# sd_tos_dip32.net
KiCad netlist of a schematic drawn in EAGLE
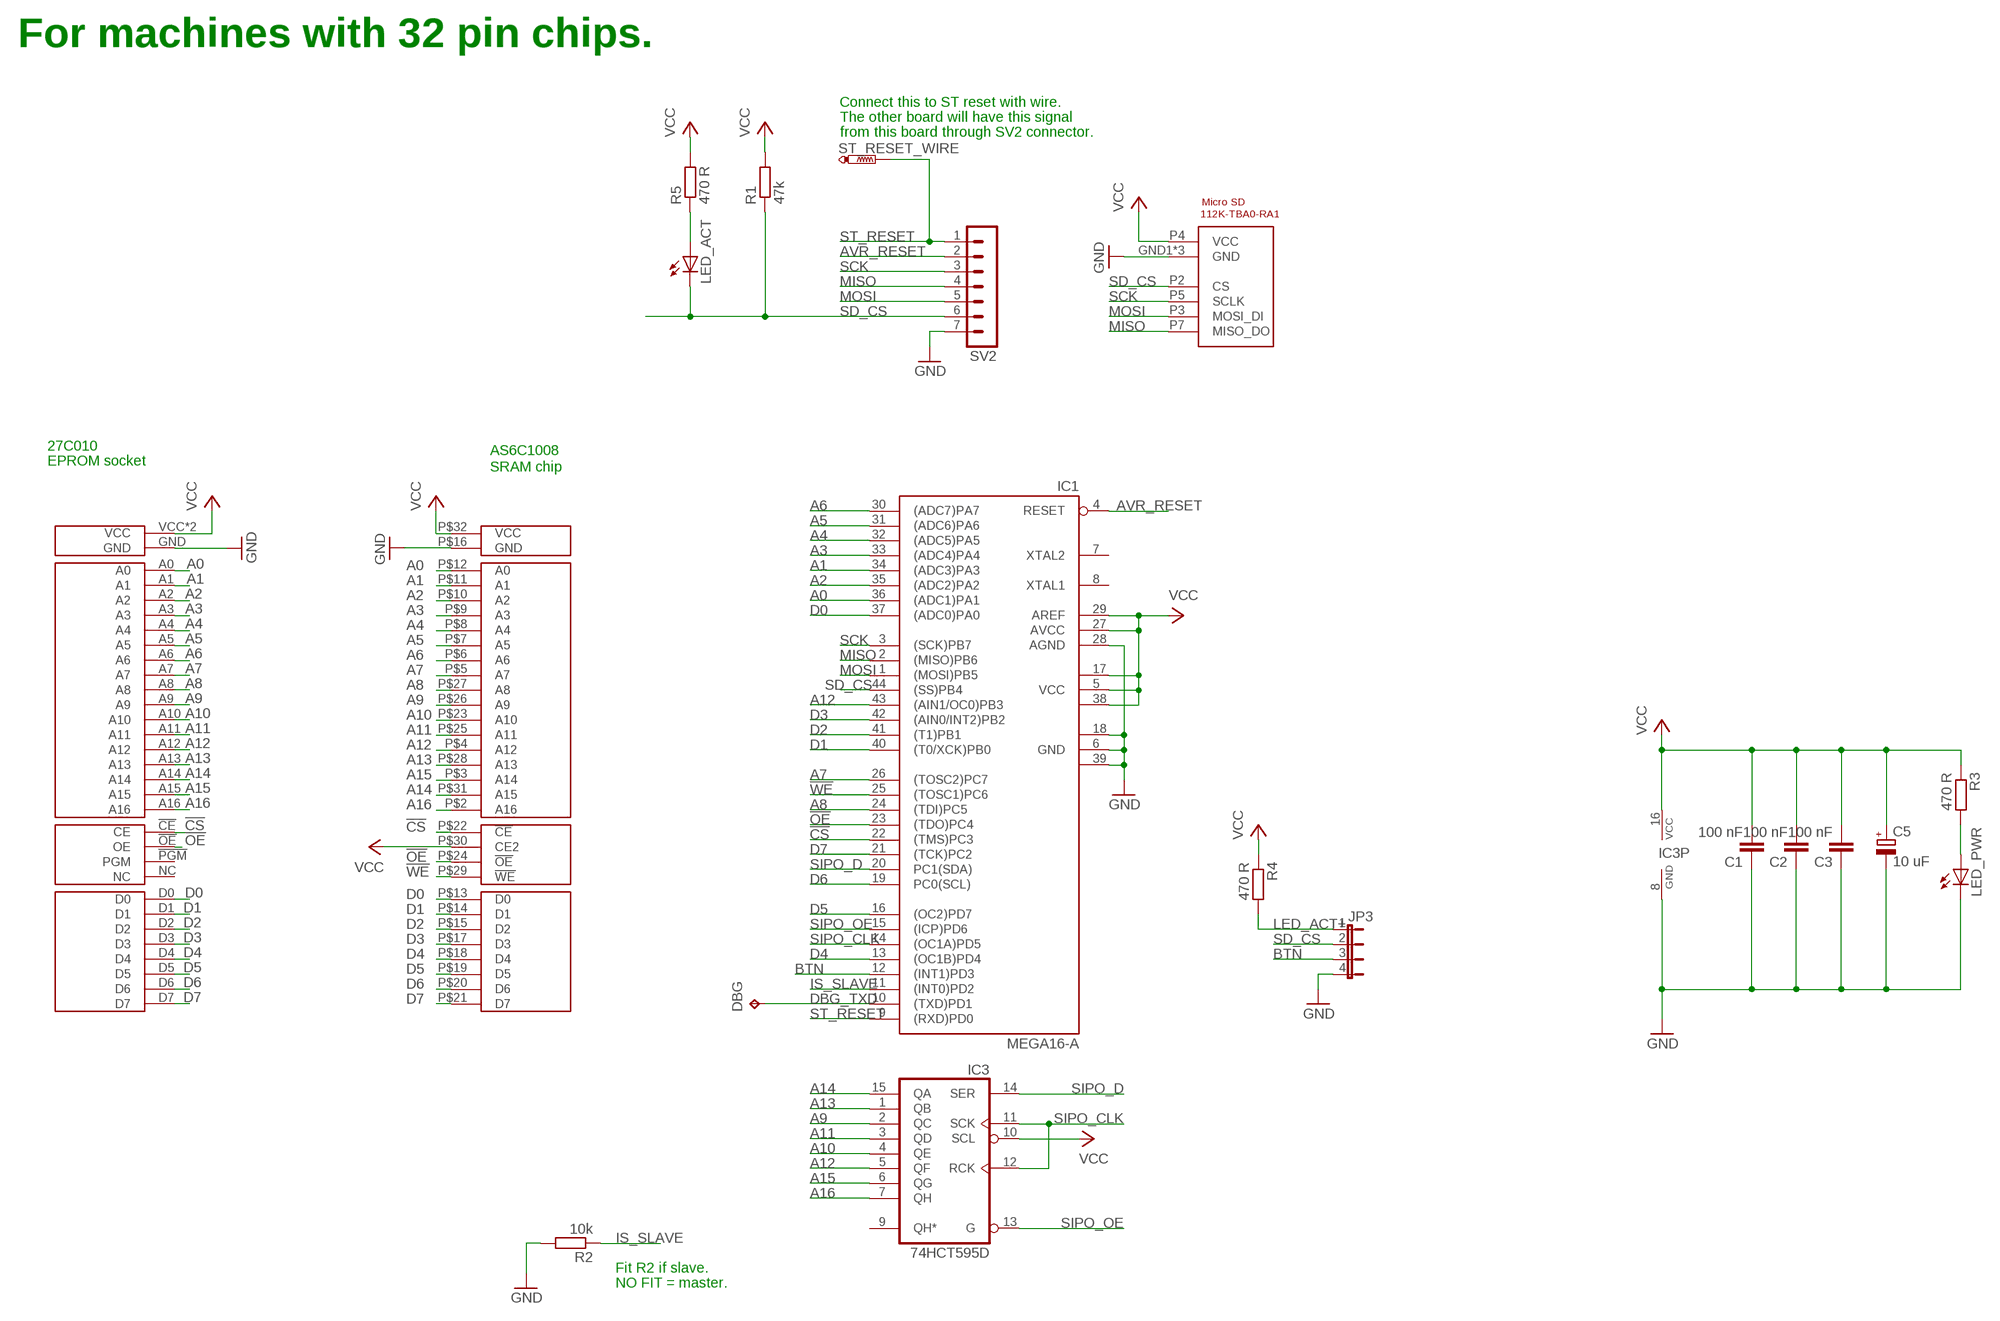
[diagram p0: schematic, sheet 1]

(export (version "E")
  (design (tool "Eeschema 10.0.6"))
  (components
    (comp (ref "C1")
      (value "100 nF")
      (footprint "eagle-import:C0603")
      (libsource (lib "eagle-import") (part "C-EUC0603"))
    )
    (comp (ref "C2")
      (value "100 nF")
      (footprint "eagle-import:C0603")
      (libsource (lib "eagle-import") (part "C-EUC0603"))
    )
    (comp (ref "C3")
      (value "100 nF")
      (footprint "eagle-import:C0603")
      (libsource (lib "eagle-import") (part "C-EUC0603"))
    )
    (comp (ref "C5")
      (value "10 uF")
      (footprint "eagle-import:SANYO-OSCON_SMD_B6")
      (libsource (lib "eagle-import") (part "CPOL-EUSANYO_SMD_B6"))
    )
    (comp (ref "DBG")
      (value "TPB1,27")
      (footprint "eagle-import:B1,27")
      (libsource (lib "eagle-import") (part "TPB1,27"))
    )
    (comp (ref "IC1")
      (value "MEGA16-A")
      (footprint "eagle-import:TQFP44")
      (libsource (lib "eagle-import") (part "MEGA16-A"))
    )
    (comp (ref "IC3")
      (value "74HCT595D")
      (footprint "eagle-import:SO16")
      (libsource (lib "eagle-import") (part "74595DHCT"))
    )
    (comp (ref "JP3")
      (value "JP4E")
      (footprint "eagle-import:JP4")
      (libsource (lib "eagle-import") (part "JP4E"))
    )
    (comp (ref "LED_ACT")
      (value "LEDCHIP-LED0805")
      (footprint "eagle-import:CHIP-LED0805")
      (libsource (lib "eagle-import") (part "LEDCHIP-LED0805"))
    )
    (comp (ref "LED_PWR")
      (value "LEDCHIP-LED0805")
      (footprint "eagle-import:CHIP-LED0805")
      (libsource (lib "eagle-import") (part "LEDCHIP-LED0805"))
    )
    (comp (ref "R1")
      (value "47k")
      (footprint "eagle-import:R0603")
      (libsource (lib "eagle-import") (part "R-EU_R0603"))
    )
    (comp (ref "R2")
      (value "10k")
      (footprint "eagle-import:R0603")
      (libsource (lib "eagle-import") (part "R-EU_R0603"))
    )
    (comp (ref "R3")
      (value "470 R")
      (footprint "eagle-import:R0603")
      (libsource (lib "eagle-import") (part "R-EU_R0603"))
    )
    (comp (ref "R4")
      (value "470 R")
      (footprint "eagle-import:R0603")
      (libsource (lib "eagle-import") (part "R-EU_R0603"))
    )
    (comp (ref "R5")
      (value "470 R")
      (footprint "eagle-import:R0603")
      (libsource (lib "eagle-import") (part "R-EU_R0603"))
    )
    (comp (ref "ST_RESET_WIRE")
      (value "PTR1PAD1-13")
      (footprint "eagle-import:P1-13")
      (libsource (lib "eagle-import") (part "PTR1PAD1-13"))
    )
    (comp (ref "SV2")
      (value "MA07-1")
      (footprint "eagle-import:MA07-1")
      (libsource (lib "eagle-import") (part "MA07-1"))
    )
    (comp (ref "U$1")
      (value "27C010_BOTTOM_ONLY")
      (footprint "eagle-import:DIP32_BOTTOM_ONLY")
      (libsource (lib "eagle-import") (part "27C010_BOTTOM_ONLY"))
    )
    (comp (ref "U$2")
      (value "AS6C1008DIP32")
      (footprint "eagle-import:DIP32")
      (libsource (lib "eagle-import") (part "AS6C1008DIP32"))
    )
    (comp (ref "U$3")
      (value "MICRO_SD")
      (footprint "eagle-import:MICRO_SD")
      (libsource (lib "eagle-import") (part "MICRO_SD"))
    )
  )
  (nets
    (net (code "1") (name "/A0") (class "Default")
      (node (ref "IC1") (pin "36") (pinfunction "(ADC1)PA1_36") (pintype "bidirectional"))
      (node (ref "U$1") (pin "A0") (pinfunction "A0_A0") (pintype "bidirectional"))
      (node (ref "U$2") (pin "P$12") (pinfunction "A0_P$12") (pintype "bidirectional"))
    )
    (net (code "2") (name "/A1") (class "Default")
      (node (ref "IC1") (pin "34") (pinfunction "(ADC3)PA3_34") (pintype "bidirectional"))
      (node (ref "U$1") (pin "A1") (pinfunction "A1_A1") (pintype "bidirectional"))
      (node (ref "U$2") (pin "P$11") (pinfunction "A1_P$11") (pintype "bidirectional"))
    )
    (net (code "3") (name "/A2") (class "Default")
      (node (ref "IC1") (pin "35") (pinfunction "(ADC2)PA2_35") (pintype "bidirectional"))
      (node (ref "U$1") (pin "A2") (pinfunction "A2_A2") (pintype "bidirectional"))
      (node (ref "U$2") (pin "P$10") (pinfunction "A2_P$10") (pintype "bidirectional"))
    )
    (net (code "4") (name "/A3") (class "Default")
      (node (ref "IC1") (pin "33") (pinfunction "(ADC4)PA4_33") (pintype "bidirectional"))
      (node (ref "U$1") (pin "A3") (pinfunction "A3_A3") (pintype "bidirectional"))
      (node (ref "U$2") (pin "P$9") (pinfunction "A3_P$9") (pintype "bidirectional"))
    )
    (net (code "5") (name "/A4") (class "Default")
      (node (ref "IC1") (pin "32") (pinfunction "(ADC5)PA5_32") (pintype "bidirectional"))
      (node (ref "U$1") (pin "A4") (pinfunction "A4_A4") (pintype "bidirectional"))
      (node (ref "U$2") (pin "P$8") (pinfunction "A4_P$8") (pintype "bidirectional"))
    )
    (net (code "6") (name "/A5") (class "Default")
      (node (ref "IC1") (pin "31") (pinfunction "(ADC6)PA6_31") (pintype "bidirectional"))
      (node (ref "U$1") (pin "A5") (pinfunction "A5_A5") (pintype "bidirectional"))
      (node (ref "U$2") (pin "P$7") (pinfunction "A5_P$7") (pintype "bidirectional"))
    )
    (net (code "7") (name "/A6") (class "Default")
      (node (ref "IC1") (pin "30") (pinfunction "(ADC7)PA7_30") (pintype "bidirectional"))
      (node (ref "U$1") (pin "A6") (pinfunction "A6_A6") (pintype "bidirectional"))
      (node (ref "U$2") (pin "P$6") (pinfunction "A6_P$6") (pintype "bidirectional"))
    )
    (net (code "8") (name "/A7") (class "Default")
      (node (ref "IC1") (pin "26") (pinfunction "(TOSC2)PC7_26") (pintype "bidirectional"))
      (node (ref "U$1") (pin "A7") (pinfunction "A7_A7") (pintype "bidirectional"))
      (node (ref "U$2") (pin "P$5") (pinfunction "A7_P$5") (pintype "bidirectional"))
    )
    (net (code "9") (name "/A8") (class "Default")
      (node (ref "IC1") (pin "24") (pinfunction "(TDI)PC5_24") (pintype "bidirectional"))
      (node (ref "U$1") (pin "A8") (pinfunction "A8_A8") (pintype "bidirectional"))
      (node (ref "U$2") (pin "P$27") (pinfunction "A8_P$27") (pintype "bidirectional"))
    )
    (net (code "10") (name "/A9") (class "Default")
      (node (ref "IC3") (pin "2") (pinfunction "QC_2") (pintype "tri_state"))
      (node (ref "U$1") (pin "A9") (pinfunction "A9_A9") (pintype "bidirectional"))
      (node (ref "U$2") (pin "P$26") (pinfunction "A9_P$26") (pintype "bidirectional"))
    )
    (net (code "11") (name "/A10") (class "Default")
      (node (ref "IC3") (pin "4") (pinfunction "QE_4") (pintype "tri_state"))
      (node (ref "U$1") (pin "A10") (pinfunction "A10_A10") (pintype "bidirectional"))
      (node (ref "U$2") (pin "P$23") (pinfunction "A10_P$23") (pintype "bidirectional"))
    )
    (net (code "12") (name "/A11") (class "Default")
      (node (ref "IC3") (pin "3") (pinfunction "QD_3") (pintype "tri_state"))
      (node (ref "U$1") (pin "A11") (pinfunction "A11_A11") (pintype "bidirectional"))
      (node (ref "U$2") (pin "P$25") (pinfunction "A11_P$25") (pintype "bidirectional"))
    )
    (net (code "13") (name "/A12") (class "Default")
      (node (ref "IC1") (pin "43") (pinfunction "(AIN1/OC0)PB3_43") (pintype "bidirectional"))
      (node (ref "IC3") (pin "5") (pinfunction "QF_5") (pintype "tri_state"))
      (node (ref "U$1") (pin "A12") (pinfunction "A12_A12") (pintype "bidirectional"))
      (node (ref "U$2") (pin "P$4") (pinfunction "A12_P$4") (pintype "bidirectional"))
    )
    (net (code "14") (name "/A13") (class "Default")
      (node (ref "IC3") (pin "1") (pinfunction "QB_1") (pintype "tri_state"))
      (node (ref "U$1") (pin "A13") (pinfunction "A13_A13") (pintype "bidirectional"))
      (node (ref "U$2") (pin "P$28") (pinfunction "A13_P$28") (pintype "bidirectional"))
    )
    (net (code "15") (name "/A14") (class "Default")
      (node (ref "IC3") (pin "15") (pinfunction "QA_15") (pintype "tri_state"))
      (node (ref "U$1") (pin "A14") (pinfunction "A14_A14") (pintype "bidirectional"))
      (node (ref "U$2") (pin "P$31") (pinfunction "A15_P$31") (pintype "bidirectional"))
    )
    (net (code "16") (name "/A15") (class "Default")
      (node (ref "IC3") (pin "6") (pinfunction "QG_6") (pintype "tri_state"))
      (node (ref "U$1") (pin "A15") (pinfunction "A15_A15") (pintype "bidirectional"))
      (node (ref "U$2") (pin "P$3") (pinfunction "A14_P$3") (pintype "bidirectional"))
    )
    (net (code "17") (name "/A16") (class "Default")
      (node (ref "IC3") (pin "7") (pinfunction "QH_7") (pintype "tri_state"))
      (node (ref "U$1") (pin "A16") (pinfunction "A16_A16") (pintype "bidirectional"))
      (node (ref "U$2") (pin "P$2") (pinfunction "A16_P$2") (pintype "bidirectional"))
    )
    (net (code "18") (name "/AVR_RESET") (class "Default")
      (node (ref "IC1") (pin "4") (pinfunction "RESET_4") (pintype "input"))
      (node (ref "SV2") (pin "2") (pinfunction "2_2") (pintype "passive"))
    )
    (net (code "19") (name "/BTN") (class "Default")
      (node (ref "IC1") (pin "12") (pinfunction "(INT1)PD3_12") (pintype "bidirectional"))
      (node (ref "JP3") (pin "3") (pinfunction "3_3") (pintype "passive"))
    )
    (net (code "20") (name "/D0") (class "Default")
      (node (ref "IC1") (pin "37") (pinfunction "(ADC0)PA0_37") (pintype "bidirectional"))
      (node (ref "U$1") (pin "D0") (pinfunction "D0_D0") (pintype "bidirectional"))
      (node (ref "U$2") (pin "P$13") (pinfunction "D0_P$13") (pintype "bidirectional"))
    )
    (net (code "21") (name "/D1") (class "Default")
      (node (ref "IC1") (pin "40") (pinfunction "(T0/XCK)PB0_40") (pintype "bidirectional"))
      (node (ref "U$1") (pin "D1") (pinfunction "D1_D1") (pintype "bidirectional"))
      (node (ref "U$2") (pin "P$14") (pinfunction "D1_P$14") (pintype "bidirectional"))
    )
    (net (code "22") (name "/D2") (class "Default")
      (node (ref "IC1") (pin "41") (pinfunction "(T1)PB1_41") (pintype "bidirectional"))
      (node (ref "U$1") (pin "D2") (pinfunction "D2_D2") (pintype "bidirectional"))
      (node (ref "U$2") (pin "P$15") (pinfunction "D2_P$15") (pintype "bidirectional"))
    )
    (net (code "23") (name "/D3") (class "Default")
      (node (ref "IC1") (pin "42") (pinfunction "(AIN0/INT2)PB2_42") (pintype "bidirectional"))
      (node (ref "U$1") (pin "D3") (pinfunction "D3_D3") (pintype "bidirectional"))
      (node (ref "U$2") (pin "P$17") (pinfunction "D3_P$17") (pintype "bidirectional"))
    )
    (net (code "24") (name "/D4") (class "Default")
      (node (ref "IC1") (pin "13") (pinfunction "(OC1B)PD4_13") (pintype "bidirectional"))
      (node (ref "U$1") (pin "D4") (pinfunction "D4_D4") (pintype "bidirectional"))
      (node (ref "U$2") (pin "P$18") (pinfunction "D4_P$18") (pintype "bidirectional"))
    )
    (net (code "25") (name "/D5") (class "Default")
      (node (ref "IC1") (pin "16") (pinfunction "(OC2)PD7_16") (pintype "bidirectional"))
      (node (ref "U$1") (pin "D5") (pinfunction "D5_D5") (pintype "bidirectional"))
      (node (ref "U$2") (pin "P$19") (pinfunction "D5_P$19") (pintype "bidirectional"))
    )
    (net (code "26") (name "/D6") (class "Default")
      (node (ref "IC1") (pin "19") (pinfunction "PC0(SCL)_19") (pintype "bidirectional"))
      (node (ref "U$1") (pin "D6") (pinfunction "D6_D6") (pintype "bidirectional"))
      (node (ref "U$2") (pin "P$20") (pinfunction "D6_P$20") (pintype "bidirectional"))
    )
    (net (code "27") (name "/D7") (class "Default")
      (node (ref "IC1") (pin "21") (pinfunction "(TCK)PC2_21") (pintype "bidirectional"))
      (node (ref "U$1") (pin "D7") (pinfunction "D7_D7") (pintype "bidirectional"))
      (node (ref "U$2") (pin "P$21") (pinfunction "D7_P$21") (pintype "bidirectional"))
    )
    (net (code "28") (name "/DBG_TXD") (class "Default")
      (node (ref "DBG") (pin "TP") (pinfunction "TP_TP") (pintype "input"))
      (node (ref "IC1") (pin "10") (pinfunction "(TXD)PD1_10") (pintype "bidirectional"))
    )
    (net (code "29") (name "/IS_SLAVE") (class "Default")
      (node (ref "IC1") (pin "11") (pinfunction "(INT0)PD2_11") (pintype "bidirectional"))
      (node (ref "R2") (pin "1") (pinfunction "1_1") (pintype "passive"))
    )
    (net (code "30") (name "/LED_ACT+") (class "Default")
      (node (ref "JP3") (pin "1") (pinfunction "1_1") (pintype "passive"))
      (node (ref "R4") (pin "2") (pinfunction "2_2") (pintype "passive"))
    )
    (net (code "31") (name "/MISO") (class "Default")
      (node (ref "IC1") (pin "2") (pinfunction "(MISO)PB6_2") (pintype "bidirectional"))
      (node (ref "SV2") (pin "4") (pinfunction "4_4") (pintype "passive"))
      (node (ref "U$3") (pin "P7") (pinfunction "MISO_DO_P7") (pintype "output"))
    )
    (net (code "32") (name "/MOSI") (class "Default")
      (node (ref "IC1") (pin "1") (pinfunction "(MOSI)PB5_1") (pintype "bidirectional"))
      (node (ref "SV2") (pin "5") (pinfunction "5_5") (pintype "passive"))
      (node (ref "U$3") (pin "P3") (pinfunction "MOSI_DI_P3") (pintype "input"))
    )
    (net (code "33") (name "/SCK") (class "Default")
      (node (ref "IC1") (pin "3") (pinfunction "(SCK)PB7_3") (pintype "bidirectional"))
      (node (ref "SV2") (pin "3") (pinfunction "3_3") (pintype "passive"))
      (node (ref "U$3") (pin "P5") (pinfunction "SCLK_P5") (pintype "input"))
    )
    (net (code "34") (name "/SD_CS") (class "Default")
      (node (ref "IC1") (pin "44") (pinfunction "(SS)PB4_44") (pintype "bidirectional"))
      (node (ref "JP3") (pin "2") (pinfunction "2_2") (pintype "passive"))
      (node (ref "LED_ACT") (pin "C") (pinfunction "C_C") (pintype "passive"))
      (node (ref "R1") (pin "1") (pinfunction "1_1") (pintype "passive"))
      (node (ref "SV2") (pin "6") (pinfunction "6_6") (pintype "passive"))
      (node (ref "U$3") (pin "P2") (pinfunction "CS_P2") (pintype "input"))
    )
    (net (code "35") (name "/SIPO_CLK") (class "Default")
      (node (ref "IC1") (pin "14") (pinfunction "(OC1A)PD5_14") (pintype "bidirectional"))
      (node (ref "IC3") (pin "11") (pinfunction "SCK_11") (pintype "input"))
      (node (ref "IC3") (pin "12") (pinfunction "RCK_12") (pintype "input"))
    )
    (net (code "36") (name "/SIPO_D") (class "Default")
      (node (ref "IC1") (pin "20") (pinfunction "PC1(SDA)_20") (pintype "bidirectional"))
      (node (ref "IC3") (pin "14") (pinfunction "SER_14") (pintype "input"))
    )
    (net (code "37") (name "/SIPO_OE") (class "Default")
      (node (ref "IC1") (pin "15") (pinfunction "(ICP)PD6_15") (pintype "bidirectional"))
      (node (ref "IC3") (pin "13") (pinfunction "G_13") (pintype "input"))
    )
    (net (code "38") (name "/ST_RESET") (class "Default")
      (node (ref "IC1") (pin "9") (pinfunction "(RXD)PD0_9") (pintype "bidirectional"))
      (node (ref "ST_RESET_WIRE") (pin "TP") (pinfunction "TP_TP") (pintype "input"))
      (node (ref "SV2") (pin "1") (pinfunction "1_1") (pintype "passive"))
    )
    (net (code "39") (name "/~{CS}") (class "Default")
      (node (ref "IC1") (pin "22") (pinfunction "(TMS)PC3_22") (pintype "bidirectional"))
      (node (ref "U$1") (pin "!CE") (pinfunction "CE_!CE") (pintype "bidirectional"))
      (node (ref "U$2") (pin "P$22") (pinfunction "~{CE}_P$22") (pintype "bidirectional"))
    )
    (net (code "40") (name "/~{OE}") (class "Default")
      (node (ref "IC1") (pin "23") (pinfunction "(TDO)PC4_23") (pintype "bidirectional"))
      (node (ref "U$1") (pin "!OE") (pinfunction "OE_!OE") (pintype "bidirectional"))
      (node (ref "U$2") (pin "P$24") (pinfunction "~{OE}_P$24") (pintype "bidirectional"))
    )
    (net (code "41") (name "/~{WE}") (class "Default")
      (node (ref "IC1") (pin "25") (pinfunction "(TOSC1)PC6_25") (pintype "bidirectional"))
      (node (ref "U$2") (pin "P$29") (pinfunction "~{WE}_P$29") (pintype "bidirectional"))
    )
    (net (code "42") (name "GND") (class "Default")
      (node (ref "C1") (pin "1") (pinfunction "1_1") (pintype "passive"))
      (node (ref "C2") (pin "1") (pinfunction "1_1") (pintype "passive"))
      (node (ref "C3") (pin "1") (pinfunction "1_1") (pintype "passive"))
      (node (ref "C5") (pin "-") (pinfunction "-_-") (pintype "passive"))
      (node (ref "IC1") (pin "18") (pinfunction "GND1_18") (pintype "power_in"))
      (node (ref "IC1") (pin "28") (pinfunction "AGND_28") (pintype "power_in"))
      (node (ref "IC1") (pin "39") (pinfunction "GND2_39") (pintype "power_in"))
      (node (ref "IC1") (pin "6") (pinfunction "GND_6") (pintype "power_in"))
      (node (ref "IC3") (pin "8") (pinfunction "GND_8") (pintype "power_in"))
      (node (ref "JP3") (pin "4") (pinfunction "4_4") (pintype "passive"))
      (node (ref "LED_PWR") (pin "C") (pinfunction "C_C") (pintype "passive"))
      (node (ref "R2") (pin "2") (pinfunction "2_2") (pintype "passive"))
      (node (ref "SV2") (pin "7") (pinfunction "7_7") (pintype "passive"))
      (node (ref "U$1") (pin "GND") (pinfunction "GND_GND") (pintype "bidirectional"))
      (node (ref "U$2") (pin "P$16") (pinfunction "GND_P$16") (pintype "bidirectional"))
      (node (ref "U$3") (pin "GND1") (pinfunction "GND_GND1") (pintype "power_in"))
      (node (ref "U$3") (pin "GND2") (pinfunction "GND_GND2") (pintype "power_in"))
      (node (ref "U$3") (pin "P6") (pinfunction "GND_P6") (pintype "power_in"))
    )
    (net (code "43") (name "Net-(LED_ACT-PadA)") (class "Default")
      (node (ref "LED_ACT") (pin "A") (pinfunction "A_A") (pintype "passive"))
      (node (ref "R5") (pin "1") (pinfunction "1_1") (pintype "passive"))
    )
    (net (code "44") (name "Net-(LED_PWR-PadA)") (class "Default")
      (node (ref "LED_PWR") (pin "A") (pinfunction "A_A") (pintype "passive"))
      (node (ref "R3") (pin "2") (pinfunction "2_2") (pintype "passive"))
    )
    (net (code "45") (name "VCC") (class "Default")
      (node (ref "C1") (pin "2") (pinfunction "2_2") (pintype "passive"))
      (node (ref "C2") (pin "2") (pinfunction "2_2") (pintype "passive"))
      (node (ref "C3") (pin "2") (pinfunction "2_2") (pintype "passive"))
      (node (ref "C5") (pin "+") (pinfunction "+_+") (pintype "passive"))
      (node (ref "IC1") (pin "17") (pinfunction "VCC1_17") (pintype "power_in"))
      (node (ref "IC1") (pin "27") (pinfunction "AVCC_27") (pintype "power_in"))
      (node (ref "IC1") (pin "29") (pinfunction "AREF_29") (pintype "power_in"))
      (node (ref "IC1") (pin "38") (pinfunction "VCC2_38") (pintype "power_in"))
      (node (ref "IC1") (pin "5") (pinfunction "VCC_5") (pintype "power_in"))
      (node (ref "IC3") (pin "10") (pinfunction "SCL_10") (pintype "input"))
      (node (ref "IC3") (pin "16") (pinfunction "VCC_16") (pintype "power_in"))
      (node (ref "R1") (pin "2") (pinfunction "2_2") (pintype "passive"))
      (node (ref "R3") (pin "1") (pinfunction "1_1") (pintype "passive"))
      (node (ref "R4") (pin "1") (pinfunction "1_1") (pintype "passive"))
      (node (ref "R5") (pin "2") (pinfunction "2_2") (pintype "passive"))
      (node (ref "U$1") (pin "VCC") (pinfunction "VCC_VCC") (pintype "bidirectional"))
      (node (ref "U$1") (pin "VPP") (pinfunction "VCC_VPP") (pintype "bidirectional"))
      (node (ref "U$2") (pin "P$30") (pinfunction "CE2_P$30") (pintype "bidirectional"))
      (node (ref "U$2") (pin "P$32") (pinfunction "VCC_P$32") (pintype "bidirectional"))
      (node (ref "U$3") (pin "P4") (pinfunction "VCC_P4") (pintype "power_in"))
    )
    (net (code "46") (name "unconnected-(IC1-XTAL1-Pad8)") (class "Default")
      (node (ref "IC1") (pin "8") (pinfunction "XTAL1_8") (pintype "bidirectional"))
    )
    (net (code "47") (name "unconnected-(IC1-XTAL2-Pad7)") (class "Default")
      (node (ref "IC1") (pin "7") (pinfunction "XTAL2_7") (pintype "bidirectional"))
    )
    (net (code "48") (name "unconnected-(IC3A-QH*-Pad9)") (class "Default")
      (node (ref "IC3") (pin "9") (pinfunction "QH*_9") (pintype "tri_state"))
    )
    (net (code "49") (name "unconnected-(U$1-PGM-Pad!PGM)") (class "Default")
      (node (ref "U$1") (pin "!PGM") (pinfunction "PGM_!PGM") (pintype "bidirectional"))
    )
    (net (code "50") (name "unconnected-(U$1-PadNC)") (class "Default")
      (node (ref "U$1") (pin "NC") (pinfunction "NC_NC") (pintype "bidirectional"))
    )
  )
)
